# CCU-2-inputs.net
KiCad netlist of a schematic drawn in Altium Designer
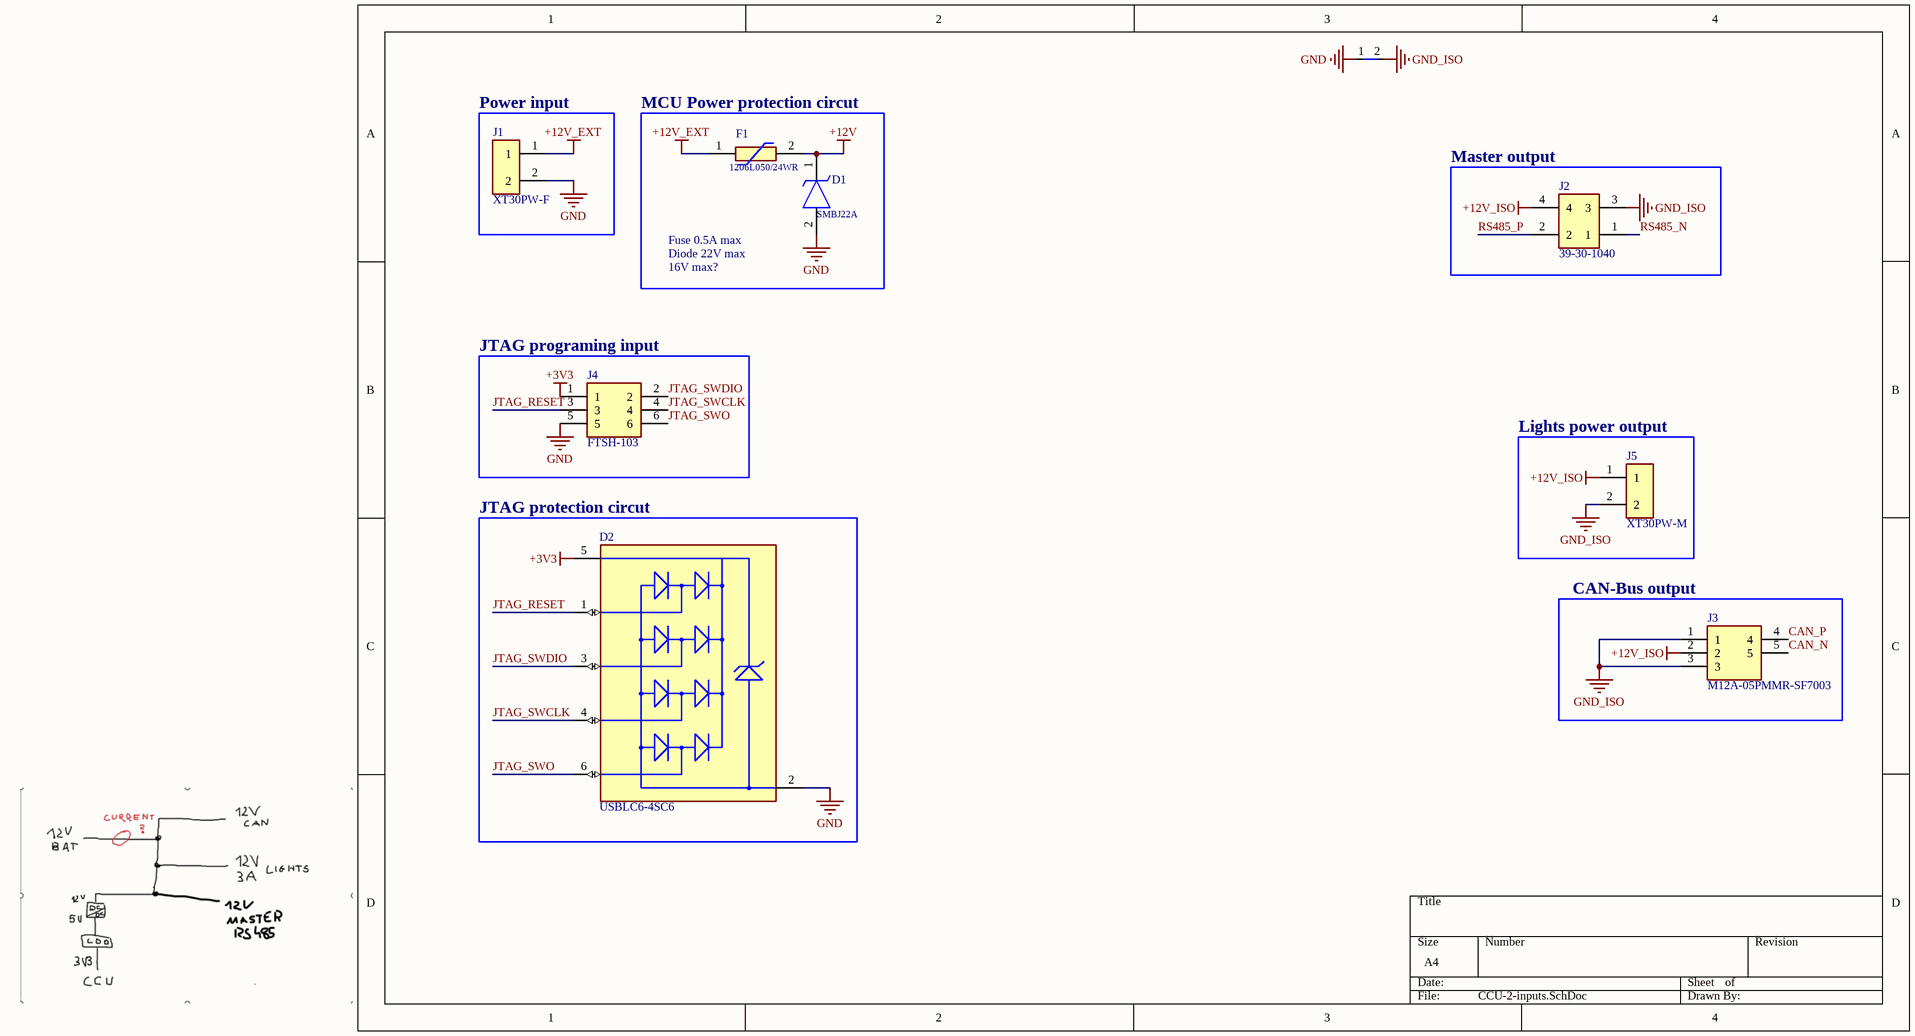
[diagram p0: CCU-2-inputs.SchDoc]

(export (version "E")
  (design (tool "Eeschema 10.0.6"))
  (components
    (comp (ref "D1")
      (value "SMBJ22A")
      (footprint "SMBJ22A")
      (description "Diode TVS Single Uni-Directional 22V 600W 2-Pin DO-214AA")
      (fields (field (name "MANUFACTURER") "Taiwan Semiconductor"))
      (libsource (lib "HydrogreenLibrary") (part "SMBJ22A"))
    )
    (comp (ref "D2")
      (value "USBLC6-4SC6")
      (footprint "FP-SOT23-6L-MFG")
      (description "TVS DIODE 5.25V 17V SOT23-6")
      (fields
        (field (name "MANUFACTURER") "STMicroelectronics")
        (field (name "OCTOPART") "https://octopart.com/usblc6-4sc6-stmicroelectronics-347147")
      )
      (libsource (lib "Altium Content Vault") (part "3e70b616ccdc4c88b528e1820c4a7da"))
    )
    (comp (ref "F1")
      (value "1206L050/24WR")
      (footprint "1206L075132WR")
      (description "1206L Series 24 V 500 mA 1206 SMT Polymeric PTC Resettable Fuse")
      (fields (field (name "MANUFACTURER") "Littelfuse"))
      (libsource (lib "HydrogreenLibrary") (part "1206L050/24WR"))
    )
    (comp (ref "J1")
      (value "XT30PW-F")
      (footprint "XT30PWF")
      (description "Socket; DC supply; XT30; female; PIN:2; on PCBs; THT; Colour: yellow")
      (libsource (lib "HydrogreenLibrary") (part "XT30PW-F"))
    )
    (comp (ref "J2")
      (value "39-30-1040")
      (footprint "39-30-1040")
      (description "Molex Connector 2x2 4.2mm Solder Right Angle Thru-Hole Tray")
      (fields (field (name "MANUFACTURER") "Molex"))
      (libsource (lib "HydrogreenLibrary") (part "39-30-1040"))
    )
    (comp (ref "J3")
      (value "M12A-05PMMR-SF7003")
      (footprint "M12A05PMMRSF7003")
      (description "M12, A Code, 4A, 05 pins, Male Contact, Hexagonal, M12*1.0, PCB 90ø, Front Fastened, IP67")
      (fields
        (field (name "MOUSER PART NUMBER") "523-M12A05PMMRSF7003")
        (field (name "MANUFACTURER") "Amphenol LTW")
      )
      (libsource (lib "HydrogreenLibrary") (part "M12A-05PMMR-SF7003"))
    )
    (comp (ref "J4")
      (value "FTSH-103")
      (footprint "FP-FTSH-103-01-L-DV-TR-MFG")
      (description "Pin Header, Board-to-Board, Wire-to-Board, 1.27 mm, 2 Rows, 6 Contacts, Surface Mount, FTSH")
      (fields
        (field (name "MANUFACTURER") "Samtec")
        (field (name "MANUFACTURER PART NUMBER") "FTSH-103-01-L-DV-TR")
      )
      (libsource (lib "HydrogreenLibrary") (part "FTSH-103-01-L-DV-TR"))
    )
    (comp (ref "J5")
      (value "XT30PW-M")
      (footprint "XT30PWM")
      (description "Plug; XT30; Male; 30A; Low Temperature Rise Fire Retardant")
      (libsource (lib "HydrogreenLibrary") (part "XT30PW-M"))
    )
    (comp (ref "NT1")
      (value "NT")
      (footprint "NetTie_SMD")
      (description "Net Tie SMD")
      (libsource (lib "HydrogreenLibrary") (part "NetTie_SMD"))
    )
  )
  (nets
    (net (code "1") (name "+3V3") (class "Default")
      (node (ref "D2") (pin "5") (pinfunction "VBUS_5") (pintype "power_in"))
      (node (ref "J4") (pin "1") (pinfunction "1_1") (pintype "passive"))
    )
    (net (code "2") (name "+12V") (class "Default")
      (node (ref "D1") (pin "1") (pinfunction "K_1") (pintype "passive"))
      (node (ref "F1") (pin "2") (pinfunction "2_2") (pintype "passive"))
    )
    (net (code "3") (name "+12V_EXT") (class "Default")
      (node (ref "F1") (pin "1") (pinfunction "1_1") (pintype "passive"))
      (node (ref "J1") (pin "1") (pinfunction "1_1") (pintype "passive"))
    )
    (net (code "4") (name "+12V_ISO") (class "Default")
      (node (ref "J2") (pin "4") (pinfunction "4_4") (pintype "passive"))
      (node (ref "J3") (pin "2") (pinfunction "2_2") (pintype "passive"))
      (node (ref "J5") (pin "1") (pinfunction "1_1") (pintype "passive"))
    )
    (net (code "5") (name "/CAN_N") (class "Default")
      (node (ref "J3") (pin "5") (pinfunction "5_5") (pintype "passive"))
    )
    (net (code "6") (name "/CAN_P") (class "Default")
      (node (ref "J3") (pin "4") (pinfunction "4_4") (pintype "passive"))
    )
    (net (code "7") (name "/JTAG_RESET") (class "Default")
      (node (ref "D2") (pin "1") (pinfunction "I/O1_1") (pintype "bidirectional"))
      (node (ref "J4") (pin "3") (pinfunction "3_3") (pintype "passive"))
    )
    (net (code "8") (name "/JTAG_SWCLK") (class "Default")
      (node (ref "D2") (pin "4") (pinfunction "I/O3_4") (pintype "bidirectional"))
      (node (ref "J4") (pin "4") (pinfunction "4_4") (pintype "passive"))
    )
    (net (code "9") (name "/JTAG_SWDIO") (class "Default")
      (node (ref "D2") (pin "3") (pinfunction "I/O2_3") (pintype "bidirectional"))
      (node (ref "J4") (pin "2") (pinfunction "2_2") (pintype "passive"))
    )
    (net (code "10") (name "/JTAG_SWO") (class "Default")
      (node (ref "D2") (pin "6") (pinfunction "I/O4_6") (pintype "bidirectional"))
      (node (ref "J4") (pin "6") (pinfunction "6_6") (pintype "passive"))
    )
    (net (code "11") (name "/RS485_N") (class "Default")
      (node (ref "J2") (pin "1") (pinfunction "1_1") (pintype "passive"))
    )
    (net (code "12") (name "/RS485_P") (class "Default")
      (node (ref "J2") (pin "2") (pinfunction "2_2") (pintype "passive"))
    )
    (net (code "13") (name "GND") (class "Default")
      (node (ref "D1") (pin "2") (pinfunction "A_2") (pintype "passive"))
      (node (ref "D2") (pin "2") (pinfunction "GND_2") (pintype "power_in"))
      (node (ref "J1") (pin "2") (pinfunction "2_2") (pintype "passive"))
      (node (ref "J4") (pin "5") (pinfunction "5_5") (pintype "passive"))
      (node (ref "NT1") (pin "1") (pinfunction "1_1") (pintype "passive"))
    )
    (net (code "14") (name "GND_ISO") (class "Default")
      (node (ref "J2") (pin "3") (pinfunction "3_3") (pintype "passive"))
      (node (ref "J3") (pin "1") (pinfunction "1_1") (pintype "passive"))
      (node (ref "J3") (pin "3") (pinfunction "3_3") (pintype "passive"))
      (node (ref "J5") (pin "2") (pinfunction "2_2") (pintype "passive"))
      (node (ref "NT1") (pin "2") (pinfunction "2_2") (pintype "passive"))
    )
  )
)
